# Microcontroller.net
KiCad netlist of a schematic drawn in Altium Designer
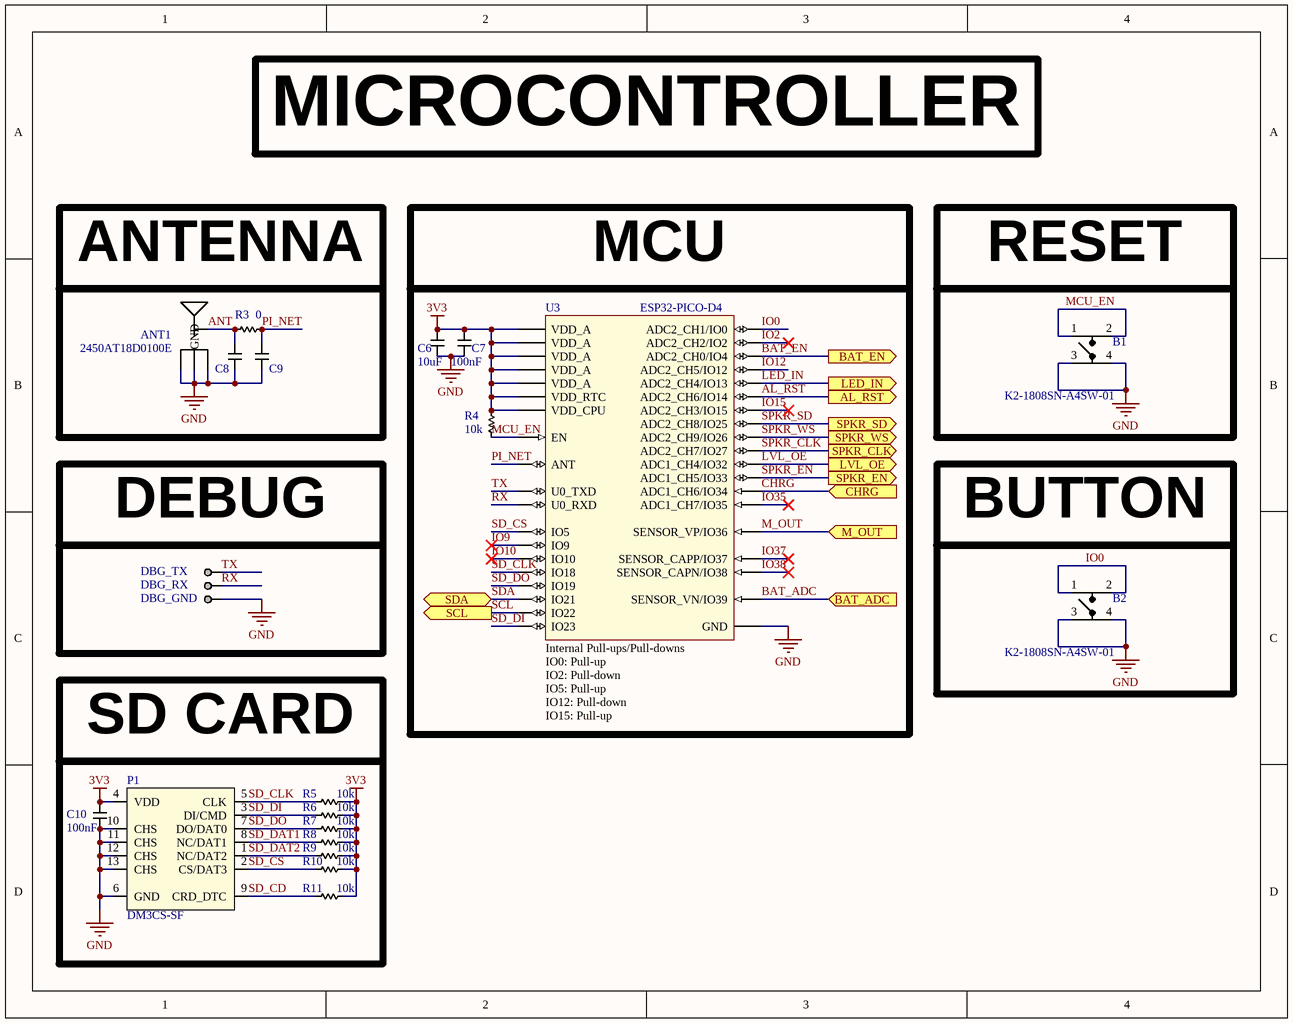
[diagram p0: Microcontroller.SchDoc]

(export (version "E")
  (design (tool "Eeschema 10.0.6"))
  (components
    (comp (ref "ANT1")
      (value "2450AT18D0100E")
      (footprint "2450AT18D0100E_RH")
      (description "2450AT18D0100E 2.4GHz  Chip RF Antenna 2.4GHz ~ 2.5GHz 1.5dBi Solder Surface Mount")
      (libsource (lib "smLib") (part "2450AT18D0100E_RH"))
    )
    (comp (ref "B1")
      (value "K2-1808SN-A4SW-01")
      (footprint "K2-1808SN-A4SW-01")
      (description "K2-1808SN-A4SW-01 Tactile Switch SPST-NO Top Actuated Surface Mount")
      (libsource (lib "smLib") (part "K2-1808SN-A4SW-01"))
    )
    (comp (ref "B2")
      (value "K2-1808SN-A4SW-01")
      (footprint "K2-1808SN-A4SW-01")
      (description "K2-1808SN-A4SW-01 Tactile Switch SPST-NO Top Actuated Surface Mount")
      (libsource (lib "smLib") (part "K2-1808SN-A4SW-01"))
    )
    (comp (ref "C6")
      (value "10uF")
      (footprint "CAP_0603_HIGH")
      (description "0603 Capacitor")
      (libsource (lib "smLib") (part "Capacitor_0603"))
    )
    (comp (ref "C7")
      (value "100nF")
      (footprint "CAP_0402_HIGH")
      (description "0402 Capacitor")
      (libsource (lib "smLib") (part "Capacitor_0402"))
    )
    (comp (ref "C8")
      (value "C")
      (footprint "CAP_0402_HIGH")
      (description "0402 Capacitor")
      (libsource (lib "smLib") (part "Capacitor_0402"))
    )
    (comp (ref "C9")
      (value "C")
      (footprint "CAP_0402_HIGH")
      (description "0402 Capacitor")
      (libsource (lib "smLib") (part "Capacitor_0402"))
    )
    (comp (ref "C10")
      (value "100nF")
      (footprint "CAP_0402_HIGH")
      (description "0402 Capacitor")
      (libsource (lib "smLib") (part "Capacitor_0402"))
    )
    (comp (ref "DBG_GND")
      (value "0.1\" Header")
      (footprint "0.1\" Header")
      (libsource (lib "smLib") (part "0.1{dblquote} Header"))
    )
    (comp (ref "DBG_RX")
      (value "0.1\" Header")
      (footprint "0.1\" Header")
      (libsource (lib "smLib") (part "0.1{dblquote} Header"))
    )
    (comp (ref "DBG_TX")
      (value "0.1\" Header")
      (footprint "0.1\" Header")
      (libsource (lib "smLib") (part "0.1{dblquote} Header"))
    )
    (comp (ref "P1") (value "DM3CS-SF") (footprint "DM3CS-SF") (libsource (lib "smLib") (part "DM3CS-SF")))
    (comp (ref "R3")
      (value "0")
      (footprint "RES_0402_HIGH")
      (description "0402 Resistor")
      (libsource (lib "smLib") (part "Resistor_0402"))
    )
    (comp (ref "R4")
      (value "10k")
      (footprint "RES_0402_HIGH")
      (description "0402 Resistor")
      (libsource (lib "smLib") (part "Resistor_0402"))
    )
    (comp (ref "R5")
      (value "10k")
      (footprint "RES_0402_HIGH")
      (description "0402 Resistor")
      (libsource (lib "smLib") (part "Resistor_0402"))
    )
    (comp (ref "R6")
      (value "10k")
      (footprint "RES_0402_HIGH")
      (description "0402 Resistor")
      (libsource (lib "smLib") (part "Resistor_0402"))
    )
    (comp (ref "R7")
      (value "10k")
      (footprint "RES_0402_HIGH")
      (description "0402 Resistor")
      (libsource (lib "smLib") (part "Resistor_0402"))
    )
    (comp (ref "R8")
      (value "10k")
      (footprint "RES_0402_HIGH")
      (description "0402 Resistor")
      (libsource (lib "smLib") (part "Resistor_0402"))
    )
    (comp (ref "R9")
      (value "10k")
      (footprint "RES_0402_HIGH")
      (description "0402 Resistor")
      (libsource (lib "smLib") (part "Resistor_0402"))
    )
    (comp (ref "R10")
      (value "10k")
      (footprint "RES_0402_HIGH")
      (description "0402 Resistor")
      (libsource (lib "smLib") (part "Resistor_0402"))
    )
    (comp (ref "R11")
      (value "10k")
      (footprint "RES_0402_HIGH")
      (description "0402 Resistor")
      (libsource (lib "smLib") (part "Resistor_0402"))
    )
    (comp (ref "U3")
      (value "ESP32-PICO-D4")
      (footprint "ESP32-PICO-D4")
      (description "ESP32-PICO-D4 SoC")
      (libsource (lib "smLib") (part "ESP32-PICO-D4"))
    )
  )
  (nets
    (net (code "1") (name "/AL_RST") (class "Default")
      (node (ref "U3") (pin "17") (pinfunction "ADC2_CH6/IO14_17") (pintype "bidirectional"))
    )
    (net (code "2") (name "/ANT") (class "Default")
      (node (ref "ANT1") (pin "1") (pinfunction "FEED_1") (pintype "passive"))
      (node (ref "C8") (pin "2") (pinfunction "2_2") (pintype "passive"))
      (node (ref "R3") (pin "1") (pinfunction "1_1") (pintype "passive"))
    )
    (net (code "3") (name "/BAT_ADC") (class "Default")
      (node (ref "U3") (pin "8") (pinfunction "SENSOR_VN/IO39_8") (pintype "input"))
    )
    (net (code "4") (name "/BAT_EN") (class "Default")
      (node (ref "U3") (pin "24") (pinfunction "ADC2_CH0/IO4_24") (pintype "bidirectional"))
    )
    (net (code "5") (name "/CHRG") (class "Default")
      (node (ref "U3") (pin "10") (pinfunction "ADC1_CH6/IO34_10") (pintype "input"))
    )
    (net (code "6") (name "/IO0") (class "Default")
      (node (ref "B2") (pin "1") (pinfunction "1_1") (pintype "passive"))
      (node (ref "B2") (pin "2") (pinfunction "2_2") (pintype "passive"))
      (node (ref "U3") (pin "23") (pinfunction "ADC2_CH1/IO0_23") (pintype "bidirectional"))
    )
    (net (code "7") (name "/IO2") (class "Default")
      (node (ref "U3") (pin "22") (pinfunction "ADC2_CH2/IO2_22") (pintype "bidirectional+no_connect"))
    )
    (net (code "8") (name "/IO9") (class "Default")
      (node (ref "U3") (pin "28") (pinfunction "IO9_28") (pintype "bidirectional+no_connect"))
    )
    (net (code "9") (name "/IO10") (class "Default")
      (node (ref "U3") (pin "29") (pinfunction "IO10_29") (pintype "bidirectional+no_connect"))
    )
    (net (code "10") (name "/IO12") (class "Default")
      (node (ref "U3") (pin "18") (pinfunction "ADC2_CH5/IO12_18") (pintype "bidirectional"))
    )
    (net (code "11") (name "/IO15") (class "Default")
      (node (ref "U3") (pin "21") (pinfunction "ADC2_CH3/IO15_21") (pintype "bidirectional+no_connect"))
    )
    (net (code "12") (name "/IO35") (class "Default")
      (node (ref "U3") (pin "11") (pinfunction "ADC1_CH7/IO35_11") (pintype "input+no_connect"))
    )
    (net (code "13") (name "/IO37") (class "Default")
      (node (ref "U3") (pin "6") (pinfunction "SENSOR_CAPP/IO37_6") (pintype "input+no_connect"))
    )
    (net (code "14") (name "/IO38") (class "Default")
      (node (ref "U3") (pin "7") (pinfunction "SENSOR_CAPN/IO38_7") (pintype "input+no_connect"))
    )
    (net (code "15") (name "/LED_IN") (class "Default")
      (node (ref "U3") (pin "20") (pinfunction "ADC2_CH4/IO13_20") (pintype "bidirectional"))
    )
    (net (code "16") (name "/LVL_OE") (class "Default")
      (node (ref "U3") (pin "12") (pinfunction "ADC1_CH4/IO32_12") (pintype "bidirectional"))
    )
    (net (code "17") (name "/MCU_EN") (class "Default")
      (node (ref "B1") (pin "1") (pinfunction "1_1") (pintype "passive"))
      (node (ref "B1") (pin "2") (pinfunction "2_2") (pintype "passive"))
      (node (ref "R4") (pin "1") (pinfunction "1_1") (pintype "passive"))
      (node (ref "U3") (pin "9") (pinfunction "EN_9") (pintype "input"))
    )
    (net (code "18") (name "/M_OUT") (class "Default")
      (node (ref "U3") (pin "5") (pinfunction "SENSOR_VP/IO36_5") (pintype "input"))
    )
    (net (code "19") (name "/PI_NET") (class "Default")
      (node (ref "C9") (pin "2") (pinfunction "2_2") (pintype "passive"))
      (node (ref "R3") (pin "2") (pinfunction "2_2") (pintype "passive"))
      (node (ref "U3") (pin "2") (pinfunction "ANT_2") (pintype "bidirectional"))
    )
    (net (code "20") (name "/RX") (class "Default")
      (node (ref "DBG_RX") (pin "1") (pinfunction "1_1") (pintype "passive"))
      (node (ref "U3") (pin "40") (pinfunction "U0_RXD_40") (pintype "bidirectional"))
    )
    (net (code "21") (name "/SCL") (class "Default")
      (node (ref "U3") (pin "39") (pinfunction "IO22_39") (pintype "bidirectional"))
    )
    (net (code "22") (name "/SDA") (class "Default")
      (node (ref "U3") (pin "42") (pinfunction "IO21_42") (pintype "bidirectional"))
    )
    (net (code "23") (name "/SD_CD") (class "Default")
      (node (ref "P1") (pin "9") (pinfunction "CRD_DTC_9") (pintype "passive"))
      (node (ref "R11") (pin "2") (pinfunction "2_2") (pintype "passive"))
    )
    (net (code "24") (name "/SD_CLK") (class "Default")
      (node (ref "P1") (pin "5") (pinfunction "CLK_5") (pintype "passive"))
      (node (ref "R5") (pin "2") (pinfunction "2_2") (pintype "passive"))
      (node (ref "U3") (pin "35") (pinfunction "IO18_35") (pintype "bidirectional"))
    )
    (net (code "25") (name "/SD_CS") (class "Default")
      (node (ref "P1") (pin "2") (pinfunction "CS/DAT3_2") (pintype "passive"))
      (node (ref "R10") (pin "2") (pinfunction "2_2") (pintype "passive"))
      (node (ref "U3") (pin "34") (pinfunction "IO5_34") (pintype "bidirectional"))
    )
    (net (code "26") (name "/SD_DAT1") (class "Default")
      (node (ref "P1") (pin "8") (pinfunction "NC/DAT1_8") (pintype "passive"))
      (node (ref "R8") (pin "2") (pinfunction "2_2") (pintype "passive"))
    )
    (net (code "27") (name "/SD_DAT2") (class "Default")
      (node (ref "P1") (pin "1") (pinfunction "NC/DAT2_1") (pintype "passive"))
      (node (ref "R9") (pin "2") (pinfunction "2_2") (pintype "passive"))
    )
    (net (code "28") (name "/SD_DI") (class "Default")
      (node (ref "P1") (pin "3") (pinfunction "DI/CMD_3") (pintype "passive"))
      (node (ref "R6") (pin "2") (pinfunction "2_2") (pintype "passive"))
      (node (ref "U3") (pin "36") (pinfunction "IO23_36") (pintype "bidirectional"))
    )
    (net (code "29") (name "/SD_DO") (class "Default")
      (node (ref "P1") (pin "7") (pinfunction "DO/DAT0_7") (pintype "passive"))
      (node (ref "R7") (pin "2") (pinfunction "2_2") (pintype "passive"))
      (node (ref "U3") (pin "38") (pinfunction "IO19_38") (pintype "bidirectional"))
    )
    (net (code "30") (name "/SPKR_CLK") (class "Default")
      (node (ref "U3") (pin "16") (pinfunction "ADC2_CH7/IO27_16") (pintype "bidirectional"))
    )
    (net (code "31") (name "/SPKR_EN") (class "Default")
      (node (ref "U3") (pin "13") (pinfunction "ADC1_CH5/IO33_13") (pintype "bidirectional"))
    )
    (net (code "32") (name "/SPKR_SD") (class "Default")
      (node (ref "U3") (pin "14") (pinfunction "ADC2_CH8/IO25_14") (pintype "bidirectional"))
    )
    (net (code "33") (name "/SPKR_WS") (class "Default")
      (node (ref "U3") (pin "15") (pinfunction "ADC2_CH9/IO26_15") (pintype "bidirectional"))
    )
    (net (code "34") (name "/TX") (class "Default")
      (node (ref "DBG_TX") (pin "1") (pinfunction "1_1") (pintype "passive"))
      (node (ref "U3") (pin "41") (pinfunction "U0_TXD_41") (pintype "bidirectional"))
    )
    (net (code "35") (name "3V3") (class "Default")
      (node (ref "C10") (pin "2") (pinfunction "2_2") (pintype "passive"))
      (node (ref "C6") (pin "2") (pinfunction "2_2") (pintype "passive"))
      (node (ref "C7") (pin "2") (pinfunction "2_2") (pintype "passive"))
      (node (ref "P1") (pin "4") (pinfunction "VDD_4") (pintype "passive"))
      (node (ref "R10") (pin "1") (pinfunction "1_1") (pintype "passive"))
      (node (ref "R11") (pin "1") (pinfunction "1_1") (pintype "passive"))
      (node (ref "R4") (pin "2") (pinfunction "2_2") (pintype "passive"))
      (node (ref "R5") (pin "1") (pinfunction "1_1") (pintype "passive"))
      (node (ref "R6") (pin "1") (pinfunction "1_1") (pintype "passive"))
      (node (ref "R7") (pin "1") (pinfunction "1_1") (pintype "passive"))
      (node (ref "R8") (pin "1") (pinfunction "1_1") (pintype "passive"))
      (node (ref "R9") (pin "1") (pinfunction "1_1") (pintype "passive"))
      (node (ref "U3") (pin "1") (pinfunction "VDD_A_1") (pintype "power_in"))
      (node (ref "U3") (pin "19") (pinfunction "VDD_RTC_19") (pintype "power_in"))
      (node (ref "U3") (pin "3") (pinfunction "VDD_A_3") (pintype "power_in"))
      (node (ref "U3") (pin "37") (pinfunction "VDD_CPU_37") (pintype "power_in"))
      (node (ref "U3") (pin "4") (pinfunction "VDD_A_4") (pintype "power_in"))
      (node (ref "U3") (pin "43") (pinfunction "VDD_A_43") (pintype "power_in"))
      (node (ref "U3") (pin "46") (pinfunction "VDD_A_46") (pintype "power_in"))
    )
    (net (code "36") (name "GND") (class "Default")
      (node (ref "ANT1") (pin "2") (pinfunction "GND_2") (pintype "passive"))
      (node (ref "ANT1") (pin "3") (pinfunction "GND_3") (pintype "passive"))
      (node (ref "ANT1") (pin "4") (pinfunction "GND_4") (pintype "passive"))
      (node (ref "B1") (pin "3") (pinfunction "3_3") (pintype "passive"))
      (node (ref "B1") (pin "4") (pinfunction "4_4") (pintype "passive"))
      (node (ref "B2") (pin "3") (pinfunction "3_3") (pintype "passive"))
      (node (ref "B2") (pin "4") (pinfunction "4_4") (pintype "passive"))
      (node (ref "C10") (pin "1") (pinfunction "1_1") (pintype "passive"))
      (node (ref "C6") (pin "1") (pinfunction "1_1") (pintype "passive"))
      (node (ref "C7") (pin "1") (pinfunction "1_1") (pintype "passive"))
      (node (ref "C8") (pin "1") (pinfunction "1_1") (pintype "passive"))
      (node (ref "C9") (pin "1") (pinfunction "1_1") (pintype "passive"))
      (node (ref "DBG_GND") (pin "1") (pinfunction "1_1") (pintype "passive"))
      (node (ref "P1") (pin "10") (pinfunction "CHS_10") (pintype "passive"))
      (node (ref "P1") (pin "11") (pinfunction "CHS_11") (pintype "passive"))
      (node (ref "P1") (pin "12") (pinfunction "CHS_12") (pintype "passive"))
      (node (ref "P1") (pin "13") (pinfunction "CHS_13") (pintype "passive"))
      (node (ref "P1") (pin "6") (pinfunction "GND_6") (pintype "passive"))
      (node (ref "U3") (pin "49") (pinfunction "GND_49") (pintype "power_in"))
    )
  )
)
